# USB_Hub.net
KiCad netlist of a schematic drawn in Altium Designer
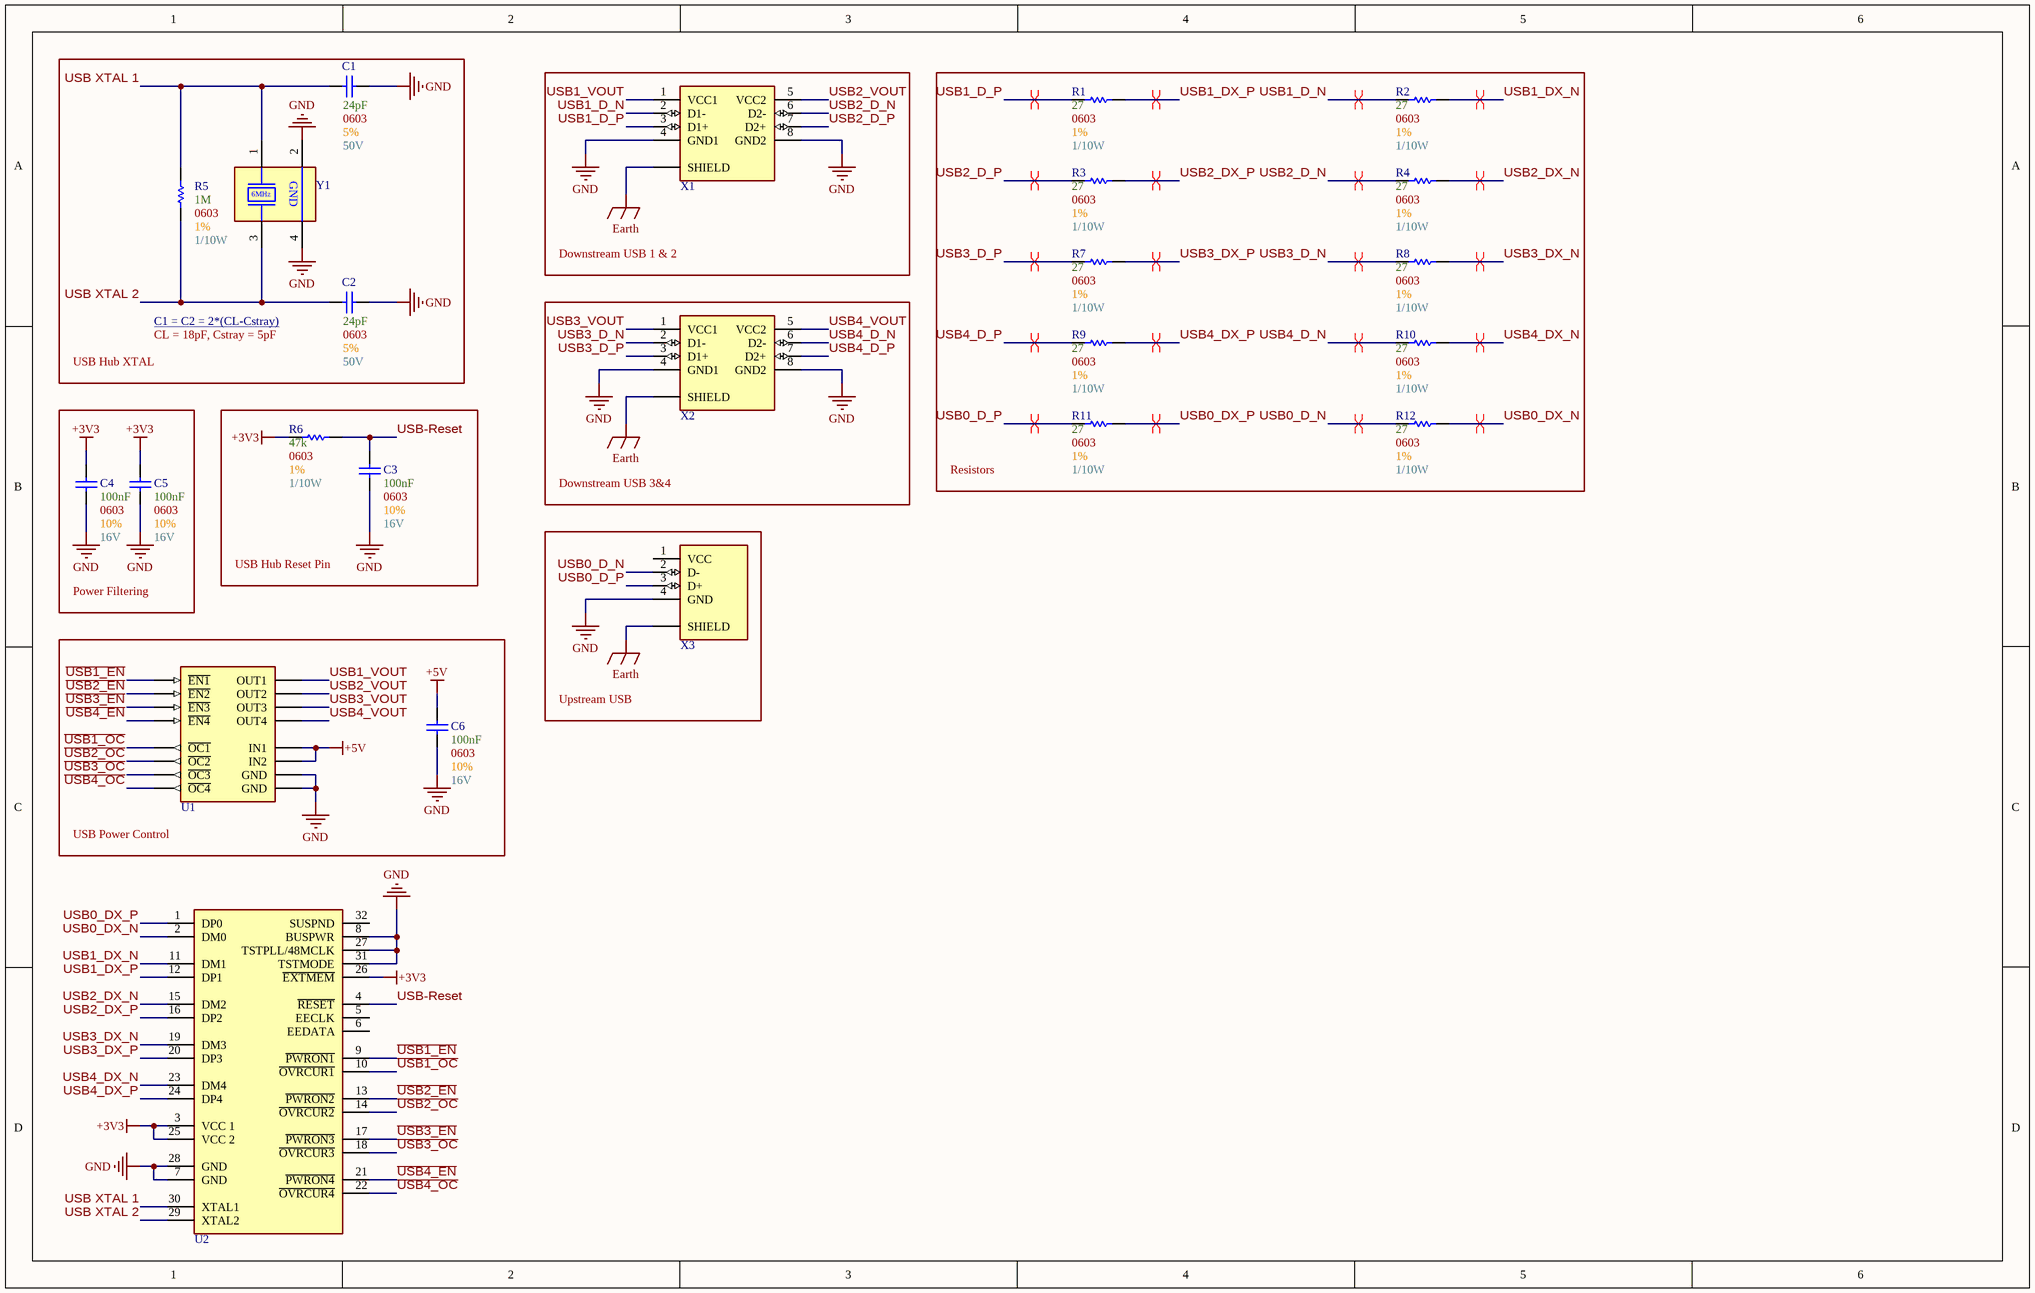
[diagram p0: USB Hub.SchDoc]

(export (version "E")
  (design (tool "Eeschema 10.0.6"))
  (components
    (comp (ref "C1")
      (value "[Cap] 0603 24pF 1% 100V")
      (footprint "[Cap] SMD 0603")
      (description "CC0603JRNPO9BN240")
      (fields
        (field (name "MAX VOLTAGE") "50V")
        (field (name "SIZE PACKAGE") "0603")
        (field (name "TOLERANCE") "5%")
        (field (name "CAPACITANCE") "24pF")
      )
      (libsource (lib "Capacitors") (part "[Cap] 0603 24pF 1% 100V"))
    )
    (comp (ref "C2")
      (value "[Cap] 0603 24pF 1% 100V")
      (footprint "[Cap] SMD 0603")
      (description "CC0603JRNPO9BN240")
      (fields
        (field (name "MAX VOLTAGE") "50V")
        (field (name "SIZE PACKAGE") "0603")
        (field (name "TOLERANCE") "5%")
        (field (name "CAPACITANCE") "24pF")
      )
      (libsource (lib "Capacitors") (part "[Cap] 0603 24pF 1% 100V"))
    )
    (comp (ref "C3")
      (value "[Cap] 0603 0.1uF 10% 16V")
      (footprint "[Cap] SMD 0603")
      (description "CC0603KRX7R7BB104")
      (fields
        (field (name "MAX VOLTAGE") "16V")
        (field (name "SIZE PACKAGE") "0603")
        (field (name "TOLERANCE") "10%")
        (field (name "CAPACITANCE") "100nF")
      )
      (libsource (lib "Capacitors") (part "[Cap] 0603 0.1uF 10% 16V"))
    )
    (comp (ref "C4")
      (value "[Cap] 0603 0.1uF 10% 16V")
      (footprint "[Cap] SMD 0603")
      (description "CC0603KRX7R7BB104")
      (fields
        (field (name "MAX VOLTAGE") "16V")
        (field (name "SIZE PACKAGE") "0603")
        (field (name "TOLERANCE") "10%")
        (field (name "CAPACITANCE") "100nF")
      )
      (libsource (lib "Capacitors") (part "[Cap] 0603 0.1uF 10% 16V"))
    )
    (comp (ref "C5")
      (value "[Cap] 0603 0.1uF 10% 16V")
      (footprint "[Cap] SMD 0603")
      (description "CC0603KRX7R7BB104")
      (fields
        (field (name "MAX VOLTAGE") "16V")
        (field (name "SIZE PACKAGE") "0603")
        (field (name "TOLERANCE") "10%")
        (field (name "CAPACITANCE") "100nF")
      )
      (libsource (lib "Capacitors") (part "[Cap] 0603 0.1uF 10% 16V"))
    )
    (comp (ref "C6")
      (value "[Cap] 0603 0.1uF 10% 16V")
      (footprint "[Cap] SMD 0603")
      (description "CC0603KRX7R7BB104")
      (fields
        (field (name "MAX VOLTAGE") "16V")
        (field (name "SIZE PACKAGE") "0603")
        (field (name "TOLERANCE") "10%")
        (field (name "CAPACITANCE") "100nF")
      )
      (libsource (lib "Capacitors") (part "[Cap] 0603 0.1uF 10% 16V"))
    )
    (comp (ref "R1")
      (value "[27] SMD 0603 1% 1/10W")
      (footprint "[Res] SMD 0603")
      (description "MCT06030C2709FP500")
      (fields
        (field (name "WATTAGE") "1/10W")
        (field (name "TOLERANCE") "1%")
        (field (name "RESISTANCE") "27")
        (field (name "SIZE PACKAGE") "0603")
      )
      (libsource (lib "Resistors") (part "[27] SMD 0603 1% 1/10W"))
    )
    (comp (ref "R2")
      (value "[27] SMD 0603 1% 1/10W")
      (footprint "[Res] SMD 0603")
      (description "MCT06030C2709FP500")
      (fields
        (field (name "WATTAGE") "1/10W")
        (field (name "TOLERANCE") "1%")
        (field (name "RESISTANCE") "27")
        (field (name "SIZE PACKAGE") "0603")
      )
      (libsource (lib "Resistors") (part "[27] SMD 0603 1% 1/10W"))
    )
    (comp (ref "R3")
      (value "[27] SMD 0603 1% 1/10W")
      (footprint "[Res] SMD 0603")
      (description "MCT06030C2709FP500")
      (fields
        (field (name "WATTAGE") "1/10W")
        (field (name "TOLERANCE") "1%")
        (field (name "RESISTANCE") "27")
        (field (name "SIZE PACKAGE") "0603")
      )
      (libsource (lib "Resistors") (part "[27] SMD 0603 1% 1/10W"))
    )
    (comp (ref "R4")
      (value "[27] SMD 0603 1% 1/10W")
      (footprint "[Res] SMD 0603")
      (description "MCT06030C2709FP500")
      (fields
        (field (name "WATTAGE") "1/10W")
        (field (name "TOLERANCE") "1%")
        (field (name "RESISTANCE") "27")
        (field (name "SIZE PACKAGE") "0603")
      )
      (libsource (lib "Resistors") (part "[27] SMD 0603 1% 1/10W"))
    )
    (comp (ref "R5")
      (value "[1M] SMD 0603 1% 1/10W")
      (footprint "[Res] SMD 0603")
      (description "RC0603FR-071ML")
      (fields
        (field (name "WATTAGE") "1/10W")
        (field (name "TOLERANCE") "1%")
        (field (name "RESISTANCE") "1M")
        (field (name "SIZE PACKAGE") "0603")
      )
      (libsource (lib "Resistors") (part "[1M] SMD 0603 1% 1/10W"))
    )
    (comp (ref "R6")
      (value "[47k] SMD 0603 1% 1/10W")
      (footprint "[Res] SMD 0603")
      (description "RC0603FR-0747KL")
      (fields
        (field (name "WATTAGE") "1/10W")
        (field (name "TOLERANCE") "1%")
        (field (name "RESISTANCE") "47k")
        (field (name "SIZE PACKAGE") "0603")
      )
      (libsource (lib "Resistors") (part "[47k] SMD 0603 1% 1/10W"))
    )
    (comp (ref "R7")
      (value "[27] SMD 0603 1% 1/10W")
      (footprint "[Res] SMD 0603")
      (description "MCT06030C2709FP500")
      (fields
        (field (name "WATTAGE") "1/10W")
        (field (name "TOLERANCE") "1%")
        (field (name "RESISTANCE") "27")
        (field (name "SIZE PACKAGE") "0603")
      )
      (libsource (lib "Resistors") (part "[27] SMD 0603 1% 1/10W"))
    )
    (comp (ref "R8")
      (value "[27] SMD 0603 1% 1/10W")
      (footprint "[Res] SMD 0603")
      (description "MCT06030C2709FP500")
      (fields
        (field (name "WATTAGE") "1/10W")
        (field (name "TOLERANCE") "1%")
        (field (name "RESISTANCE") "27")
        (field (name "SIZE PACKAGE") "0603")
      )
      (libsource (lib "Resistors") (part "[27] SMD 0603 1% 1/10W"))
    )
    (comp (ref "R9")
      (value "[27] SMD 0603 1% 1/10W")
      (footprint "[Res] SMD 0603")
      (description "MCT06030C2709FP500")
      (fields
        (field (name "WATTAGE") "1/10W")
        (field (name "TOLERANCE") "1%")
        (field (name "RESISTANCE") "27")
        (field (name "SIZE PACKAGE") "0603")
      )
      (libsource (lib "Resistors") (part "[27] SMD 0603 1% 1/10W"))
    )
    (comp (ref "R10")
      (value "[27] SMD 0603 1% 1/10W")
      (footprint "[Res] SMD 0603")
      (description "MCT06030C2709FP500")
      (fields
        (field (name "WATTAGE") "1/10W")
        (field (name "TOLERANCE") "1%")
        (field (name "RESISTANCE") "27")
        (field (name "SIZE PACKAGE") "0603")
      )
      (libsource (lib "Resistors") (part "[27] SMD 0603 1% 1/10W"))
    )
    (comp (ref "R11")
      (value "[27] SMD 0603 1% 1/10W")
      (footprint "[Res] SMD 0603")
      (description "MCT06030C2709FP500")
      (fields
        (field (name "WATTAGE") "1/10W")
        (field (name "TOLERANCE") "1%")
        (field (name "RESISTANCE") "27")
        (field (name "SIZE PACKAGE") "0603")
      )
      (libsource (lib "Resistors") (part "[27] SMD 0603 1% 1/10W"))
    )
    (comp (ref "R12")
      (value "[27] SMD 0603 1% 1/10W")
      (footprint "[Res] SMD 0603")
      (description "MCT06030C2709FP500")
      (fields
        (field (name "WATTAGE") "1/10W")
        (field (name "TOLERANCE") "1%")
        (field (name "RESISTANCE") "27")
        (field (name "SIZE PACKAGE") "0603")
      )
      (libsource (lib "Resistors") (part "[27] SMD 0603 1% 1/10W"))
    )
    (comp (ref "U1")
      (value "[USB Power] 500mA 4port")
      (footprint "[IC] USB Hub Power Distribution")
      (description "TPS2044BDR")
      (libsource (lib "ICs") (part "[USB Power] 500mA 4port"))
    )
    (comp (ref "U2")
      (value "4port")
      (footprint "[USB Hub] USB2.0 4port")
      (description "TUSB2046BVFR")
      (libsource (lib "ICs") (part "[USB Hub] USB 2.0 4port"))
    )
    (comp (ref "X1")
      (value "USB-A")
      (footprint "[USB] Type-A Dual")
      (description "61400826021")
      (libsource (lib "Connectors") (part "[USB] Type-A Dual"))
    )
    (comp (ref "X2")
      (value "USB-A")
      (footprint "[USB] Type-A Dual")
      (description "61400826021")
      (libsource (lib "Connectors") (part "[USB] Type-A Dual"))
    )
    (comp (ref "X3")
      (value "USB-A")
      (footprint "[USB] Type-A")
      (description "KUSBEX-ASFS1N-B")
      (libsource (lib "Connectors") (part "[USB] Type-A"))
    )
    (comp (ref "Y1")
      (value "[Crystal] SMD 6MHz")
      (footprint "[Crystal] SMD 6MHz")
      (description "ECS-060-18-20BM-JEN-TR")
      (libsource (lib "Crystals and Oscillators") (part "[Crystal] SMD 6MHz"))
    )
  )
  (nets
    (net (code "1") (name "+3V3") (class "Default")
      (node (ref "C4") (pin "2") (pinfunction "2_2") (pintype "passive"))
      (node (ref "C5") (pin "2") (pinfunction "2_2") (pintype "passive"))
      (node (ref "R6") (pin "1") (pinfunction "1_1") (pintype "passive"))
      (node (ref "U2") (pin "25") (pinfunction "VCC_2_25") (pintype "passive"))
      (node (ref "U2") (pin "26") (pinfunction "~{EXTMEM}_26") (pintype "passive"))
      (node (ref "U2") (pin "3") (pinfunction "VCC_1_3") (pintype "passive"))
    )
    (net (code "2") (name "+5V") (class "Default")
      (node (ref "C6") (pin "2") (pinfunction "2_2") (pintype "passive"))
      (node (ref "U1") (pin "2") (pinfunction "IN1_2") (pintype "power_in"))
      (node (ref "U1") (pin "6") (pinfunction "IN2_6") (pintype "power_in"))
    )
    (net (code "3") (name "/USB XTAL 1") (class "Default")
      (node (ref "C1") (pin "1") (pinfunction "1_1") (pintype "passive"))
      (node (ref "R5") (pin "2") (pinfunction "2_2") (pintype "passive"))
      (node (ref "U2") (pin "30") (pinfunction "XTAL1_30") (pintype "passive"))
      (node (ref "Y1") (pin "1") (pinfunction "XTAL1_1") (pintype "power_in"))
    )
    (net (code "4") (name "/USB XTAL 2") (class "Default")
      (node (ref "C2") (pin "1") (pinfunction "1_1") (pintype "passive"))
      (node (ref "R5") (pin "1") (pinfunction "1_1") (pintype "passive"))
      (node (ref "U2") (pin "29") (pinfunction "XTAL2_29") (pintype "passive"))
      (node (ref "Y1") (pin "3") (pinfunction "XTAL2_3") (pintype "power_in"))
    )
    (net (code "5") (name "/USB-Reset") (class "Default")
      (node (ref "C3") (pin "2") (pinfunction "2_2") (pintype "passive"))
      (node (ref "R6") (pin "2") (pinfunction "2_2") (pintype "passive"))
      (node (ref "U2") (pin "4") (pinfunction "~{RESET}_4") (pintype "passive"))
    )
    (net (code "6") (name "/USB0_DX_N") (class "Default")
      (node (ref "R12") (pin "2") (pinfunction "2_2") (pintype "passive"))
      (node (ref "U2") (pin "2") (pinfunction "DM0_2") (pintype "passive"))
    )
    (net (code "7") (name "/USB0_DX_P") (class "Default")
      (node (ref "R11") (pin "2") (pinfunction "2_2") (pintype "passive"))
      (node (ref "U2") (pin "1") (pinfunction "DP0_1") (pintype "passive"))
    )
    (net (code "8") (name "/USB0_D_N") (class "Default")
      (node (ref "R12") (pin "1") (pinfunction "1_1") (pintype "passive"))
      (node (ref "X3") (pin "2") (pinfunction "D-_2") (pintype "bidirectional"))
    )
    (net (code "9") (name "/USB0_D_P") (class "Default")
      (node (ref "R11") (pin "1") (pinfunction "1_1") (pintype "passive"))
      (node (ref "X3") (pin "3") (pinfunction "D+_3") (pintype "bidirectional"))
    )
    (net (code "10") (name "/USB1_DX_N") (class "Default")
      (node (ref "R2") (pin "2") (pinfunction "2_2") (pintype "passive"))
      (node (ref "U2") (pin "11") (pinfunction "DM1_11") (pintype "passive"))
    )
    (net (code "11") (name "/USB1_DX_P") (class "Default")
      (node (ref "R1") (pin "2") (pinfunction "2_2") (pintype "passive"))
      (node (ref "U2") (pin "12") (pinfunction "DP1_12") (pintype "passive"))
    )
    (net (code "12") (name "/USB1_D_N") (class "Default")
      (node (ref "R2") (pin "1") (pinfunction "1_1") (pintype "passive"))
      (node (ref "X1") (pin "2") (pinfunction "D1-_2") (pintype "bidirectional"))
    )
    (net (code "13") (name "/USB1_D_P") (class "Default")
      (node (ref "R1") (pin "1") (pinfunction "1_1") (pintype "passive"))
      (node (ref "X1") (pin "3") (pinfunction "D1+_3") (pintype "bidirectional"))
    )
    (net (code "14") (name "/USB1_EN") (class "Default")
      (node (ref "U1") (pin "3") (pinfunction "~{EN1}_3") (pintype "input"))
      (node (ref "U2") (pin "9") (pinfunction "~{PWRON1}_9") (pintype "passive"))
    )
    (net (code "15") (name "/USB1_OC") (class "Default")
      (node (ref "U1") (pin "16") (pinfunction "~{OC1}_16") (pintype "output"))
      (node (ref "U2") (pin "10") (pinfunction "~{OVRCUR1}_10") (pintype "passive"))
    )
    (net (code "16") (name "/USB1_VOUT") (class "Default")
      (node (ref "U1") (pin "15") (pinfunction "OUT1_15") (pintype "power_in"))
      (node (ref "X1") (pin "1") (pinfunction "VCC1_1") (pintype "power_in"))
    )
    (net (code "17") (name "/USB2_DX_N") (class "Default")
      (node (ref "R4") (pin "2") (pinfunction "2_2") (pintype "passive"))
      (node (ref "U2") (pin "15") (pinfunction "DM2_15") (pintype "passive"))
    )
    (net (code "18") (name "/USB2_DX_P") (class "Default")
      (node (ref "R3") (pin "2") (pinfunction "2_2") (pintype "passive"))
      (node (ref "U2") (pin "16") (pinfunction "DP2_16") (pintype "passive"))
    )
    (net (code "19") (name "/USB2_D_N") (class "Default")
      (node (ref "R4") (pin "1") (pinfunction "1_1") (pintype "passive"))
      (node (ref "X1") (pin "6") (pinfunction "D2-_6") (pintype "bidirectional"))
    )
    (net (code "20") (name "/USB2_D_P") (class "Default")
      (node (ref "R3") (pin "1") (pinfunction "1_1") (pintype "passive"))
      (node (ref "X1") (pin "7") (pinfunction "D2+_7") (pintype "bidirectional"))
    )
    (net (code "21") (name "/USB2_EN") (class "Default")
      (node (ref "U1") (pin "4") (pinfunction "~{EN2}_4") (pintype "input"))
      (node (ref "U2") (pin "13") (pinfunction "~{PWRON2}_13") (pintype "passive"))
    )
    (net (code "22") (name "/USB2_OC") (class "Default")
      (node (ref "U1") (pin "13") (pinfunction "~{OC2}_13") (pintype "output"))
      (node (ref "U2") (pin "14") (pinfunction "~{OVRCUR2}_14") (pintype "passive"))
    )
    (net (code "23") (name "/USB2_VOUT") (class "Default")
      (node (ref "U1") (pin "14") (pinfunction "OUT2_14") (pintype "power_in"))
      (node (ref "X1") (pin "5") (pinfunction "VCC2_5") (pintype "power_in"))
    )
    (net (code "24") (name "/USB3_DX_N") (class "Default")
      (node (ref "R8") (pin "2") (pinfunction "2_2") (pintype "passive"))
      (node (ref "U2") (pin "19") (pinfunction "DM3_19") (pintype "passive"))
    )
    (net (code "25") (name "/USB3_DX_P") (class "Default")
      (node (ref "R7") (pin "2") (pinfunction "2_2") (pintype "passive"))
      (node (ref "U2") (pin "20") (pinfunction "DP3_20") (pintype "passive"))
    )
    (net (code "26") (name "/USB3_D_N") (class "Default")
      (node (ref "R8") (pin "1") (pinfunction "1_1") (pintype "passive"))
      (node (ref "X2") (pin "2") (pinfunction "D1-_2") (pintype "bidirectional"))
    )
    (net (code "27") (name "/USB3_D_P") (class "Default")
      (node (ref "R7") (pin "1") (pinfunction "1_1") (pintype "passive"))
      (node (ref "X2") (pin "3") (pinfunction "D1+_3") (pintype "bidirectional"))
    )
    (net (code "28") (name "/USB3_EN") (class "Default")
      (node (ref "U1") (pin "7") (pinfunction "~{EN3}_7") (pintype "input"))
      (node (ref "U2") (pin "17") (pinfunction "~{PWRON3}_17") (pintype "passive"))
    )
    (net (code "29") (name "/USB3_OC") (class "Default")
      (node (ref "U1") (pin "12") (pinfunction "~{OC3}_12") (pintype "output"))
      (node (ref "U2") (pin "18") (pinfunction "~{OVRCUR3}_18") (pintype "passive"))
    )
    (net (code "30") (name "/USB3_VOUT") (class "Default")
      (node (ref "U1") (pin "11") (pinfunction "OUT3_11") (pintype "power_in"))
      (node (ref "X2") (pin "1") (pinfunction "VCC1_1") (pintype "power_in"))
    )
    (net (code "31") (name "/USB4_DX_N") (class "Default")
      (node (ref "R10") (pin "2") (pinfunction "2_2") (pintype "passive"))
      (node (ref "U2") (pin "23") (pinfunction "DM4_23") (pintype "passive"))
    )
    (net (code "32") (name "/USB4_DX_P") (class "Default")
      (node (ref "R9") (pin "2") (pinfunction "2_2") (pintype "passive"))
      (node (ref "U2") (pin "24") (pinfunction "DP4_24") (pintype "passive"))
    )
    (net (code "33") (name "/USB4_D_N") (class "Default")
      (node (ref "R10") (pin "1") (pinfunction "1_1") (pintype "passive"))
      (node (ref "X2") (pin "6") (pinfunction "D2-_6") (pintype "bidirectional"))
    )
    (net (code "34") (name "/USB4_D_P") (class "Default")
      (node (ref "R9") (pin "1") (pinfunction "1_1") (pintype "passive"))
      (node (ref "X2") (pin "7") (pinfunction "D2+_7") (pintype "bidirectional"))
    )
    (net (code "35") (name "/USB4_EN") (class "Default")
      (node (ref "U1") (pin "8") (pinfunction "~{EN4}_8") (pintype "input"))
      (node (ref "U2") (pin "21") (pinfunction "~{PWRON4}_21") (pintype "passive"))
    )
    (net (code "36") (name "/USB4_OC") (class "Default")
      (node (ref "U1") (pin "9") (pinfunction "~{OC4}_9") (pintype "output"))
      (node (ref "U2") (pin "22") (pinfunction "~{OVRCUR4}_22") (pintype "passive"))
    )
    (net (code "37") (name "/USB4_VOUT") (class "Default")
      (node (ref "U1") (pin "10") (pinfunction "OUT4_10") (pintype "power_in"))
      (node (ref "X2") (pin "5") (pinfunction "VCC2_5") (pintype "power_in"))
    )
    (net (code "38") (name "Earth") (class "Default")
      (node (ref "X1") (pin "MH") (pinfunction "SHIELD_MH") (pintype "passive"))
      (node (ref "X2") (pin "MH") (pinfunction "SHIELD_MH") (pintype "passive"))
      (node (ref "X3") (pin "MH") (pinfunction "SHIELD_MH") (pintype "passive"))
    )
    (net (code "39") (name "GND") (class "Default")
      (node (ref "C1") (pin "2") (pinfunction "2_2") (pintype "passive"))
      (node (ref "C2") (pin "2") (pinfunction "2_2") (pintype "passive"))
      (node (ref "C3") (pin "1") (pinfunction "1_1") (pintype "passive"))
      (node (ref "C4") (pin "1") (pinfunction "1_1") (pintype "passive"))
      (node (ref "C5") (pin "1") (pinfunction "1_1") (pintype "passive"))
      (node (ref "C6") (pin "1") (pinfunction "1_1") (pintype "passive"))
      (node (ref "U1") (pin "1") (pinfunction "GND_1") (pintype "power_in"))
      (node (ref "U1") (pin "5") (pinfunction "GND_5") (pintype "power_in"))
      (node (ref "U2") (pin "27") (pinfunction "TSTPLL/48MCLK_27") (pintype "passive"))
      (node (ref "U2") (pin "28") (pinfunction "GND_28") (pintype "passive"))
      (node (ref "U2") (pin "31") (pinfunction "TSTMODE_31") (pintype "passive"))
      (node (ref "U2") (pin "7") (pinfunction "GND_7") (pintype "passive"))
      (node (ref "U2") (pin "8") (pinfunction "BUSPWR_8") (pintype "passive"))
      (node (ref "X1") (pin "4") (pinfunction "GND1_4") (pintype "power_in"))
      (node (ref "X1") (pin "8") (pinfunction "GND2_8") (pintype "power_in"))
      (node (ref "X2") (pin "4") (pinfunction "GND1_4") (pintype "power_in"))
      (node (ref "X2") (pin "8") (pinfunction "GND2_8") (pintype "power_in"))
      (node (ref "X3") (pin "4") (pinfunction "GND_4") (pintype "power_in"))
      (node (ref "Y1") (pin "2") (pinfunction "GND_2") (pintype "power_in"))
      (node (ref "Y1") (pin "4") (pinfunction "GND_4") (pintype "power_in"))
    )
    (net (code "40") (name "unconnected-(U2-EECLK-Pad5)") (class "Default")
      (node (ref "U2") (pin "5") (pinfunction "EECLK_5") (pintype "passive"))
    )
    (net (code "41") (name "unconnected-(U2-EEDATA-Pad6)") (class "Default")
      (node (ref "U2") (pin "6") (pinfunction "EEDATA_6") (pintype "passive"))
    )
    (net (code "42") (name "unconnected-(U2-SUSPND-Pad32)") (class "Default")
      (node (ref "U2") (pin "32") (pinfunction "SUSPND_32") (pintype "passive"))
    )
    (net (code "43") (name "unconnected-(X3-VCC-Pad1)") (class "Default")
      (node (ref "X3") (pin "1") (pinfunction "VCC_1") (pintype "power_in"))
    )
  )
)
